# pca10112_sheet3_pin_map.net
KiCad netlist of a schematic drawn in Altium Designer
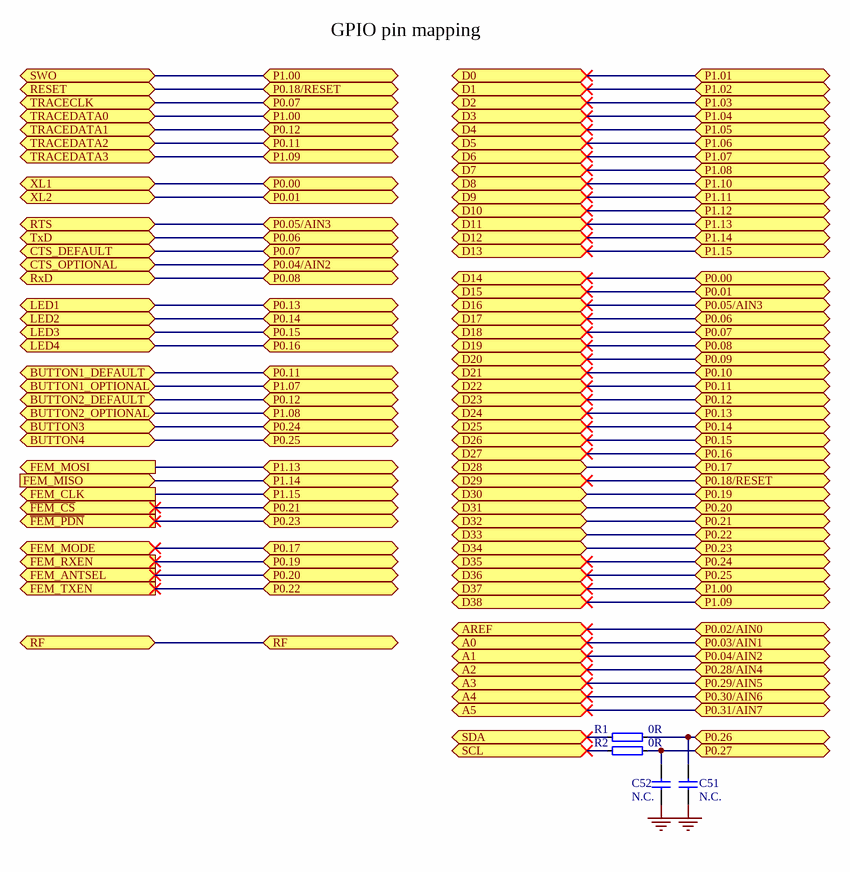
[diagram p0: pca10112_sheet3_pin_map.SchDoc]

(export (version "E")
  (design (tool "Eeschema 10.0.6"))
  (components
    (comp (ref "C51")
      (value "N.C.")
      (footprint "CAPC0603X03L_C")
      (description "Not mounted")
      (fields
        (field (name "PART NUMBER") "C0201-N.C.")
        (field (name "MANUFACTURER") "N.A.")
        (field (name "PUBLISHER") "Nordic Semiconductor")
        (field (name "AUTHOR") "rsk")
      )
      (libsource (lib "AltiumLib") (part "CAP"))
    )
    (comp (ref "C52")
      (value "N.C.")
      (footprint "CAPC0603X03L_C")
      (description "Not mounted")
      (fields
        (field (name "PART NUMBER") "C0201-N.C.")
        (field (name "MANUFACTURER") "N.A.")
        (field (name "PUBLISHER") "Nordic Semiconductor")
        (field (name "AUTHOR") "rsk")
      )
      (libsource (lib "AltiumLib") (part "CAP"))
    )
    (comp (ref "R1")
      (value "0R")
      (footprint "RESC0603X03L_C")
      (description "Resistor, ±5%, 0.05W")
      (fields
        (field (name "PART NUMBER") "R0201-0R")
        (field (name "MANUFACTURER") "N.A.")
        (field (name "PUBLISHER") "Nordic Semiconductor")
        (field (name "AUTHOR") "rsk")
      )
      (libsource (lib "AltiumLib") (part "RES_1"))
    )
    (comp (ref "R2")
      (value "0R")
      (footprint "RESC0603X03L_C")
      (description "Resistor, ±5%, 0.05W")
      (fields
        (field (name "PART NUMBER") "R0201-0R")
        (field (name "MANUFACTURER") "N.A.")
        (field (name "PUBLISHER") "Nordic Semiconductor")
        (field (name "AUTHOR") "rsk")
      )
      (libsource (lib "AltiumLib") (part "RES_1"))
    )
  )
  (nets
    (net (code "47") (name "/P0.26") (class "Default")
      (node (ref "C51") (pin "2") (pinfunction "2_2") (pintype "passive"))
      (node (ref "R1") (pin "2") (pinfunction "2_2") (pintype "passive"))
    )
    (net (code "48") (name "/P0.27") (class "Default")
      (node (ref "C52") (pin "1") (pinfunction "1_1") (pintype "passive"))
      (node (ref "R2") (pin "2") (pinfunction "2_2") (pintype "passive"))
    )
    (net (code "50") (name "/SCL") (class "Default")
      (node (ref "R2") (pin "1") (pinfunction "1_1") (pintype "passive+no_connect"))
    )
    (net (code "51") (name "/SDA") (class "Default")
      (node (ref "R1") (pin "1") (pinfunction "1_1") (pintype "passive+no_connect"))
    )
    (net (code "52") (name "GND") (class "Default")
      (node (ref "C51") (pin "1") (pinfunction "1_1") (pintype "passive"))
      (node (ref "C52") (pin "2") (pinfunction "2_2") (pintype "passive"))
    )
  )
)
